# Audio_ADC.net
KiCad netlist of a schematic drawn in Altium Designer
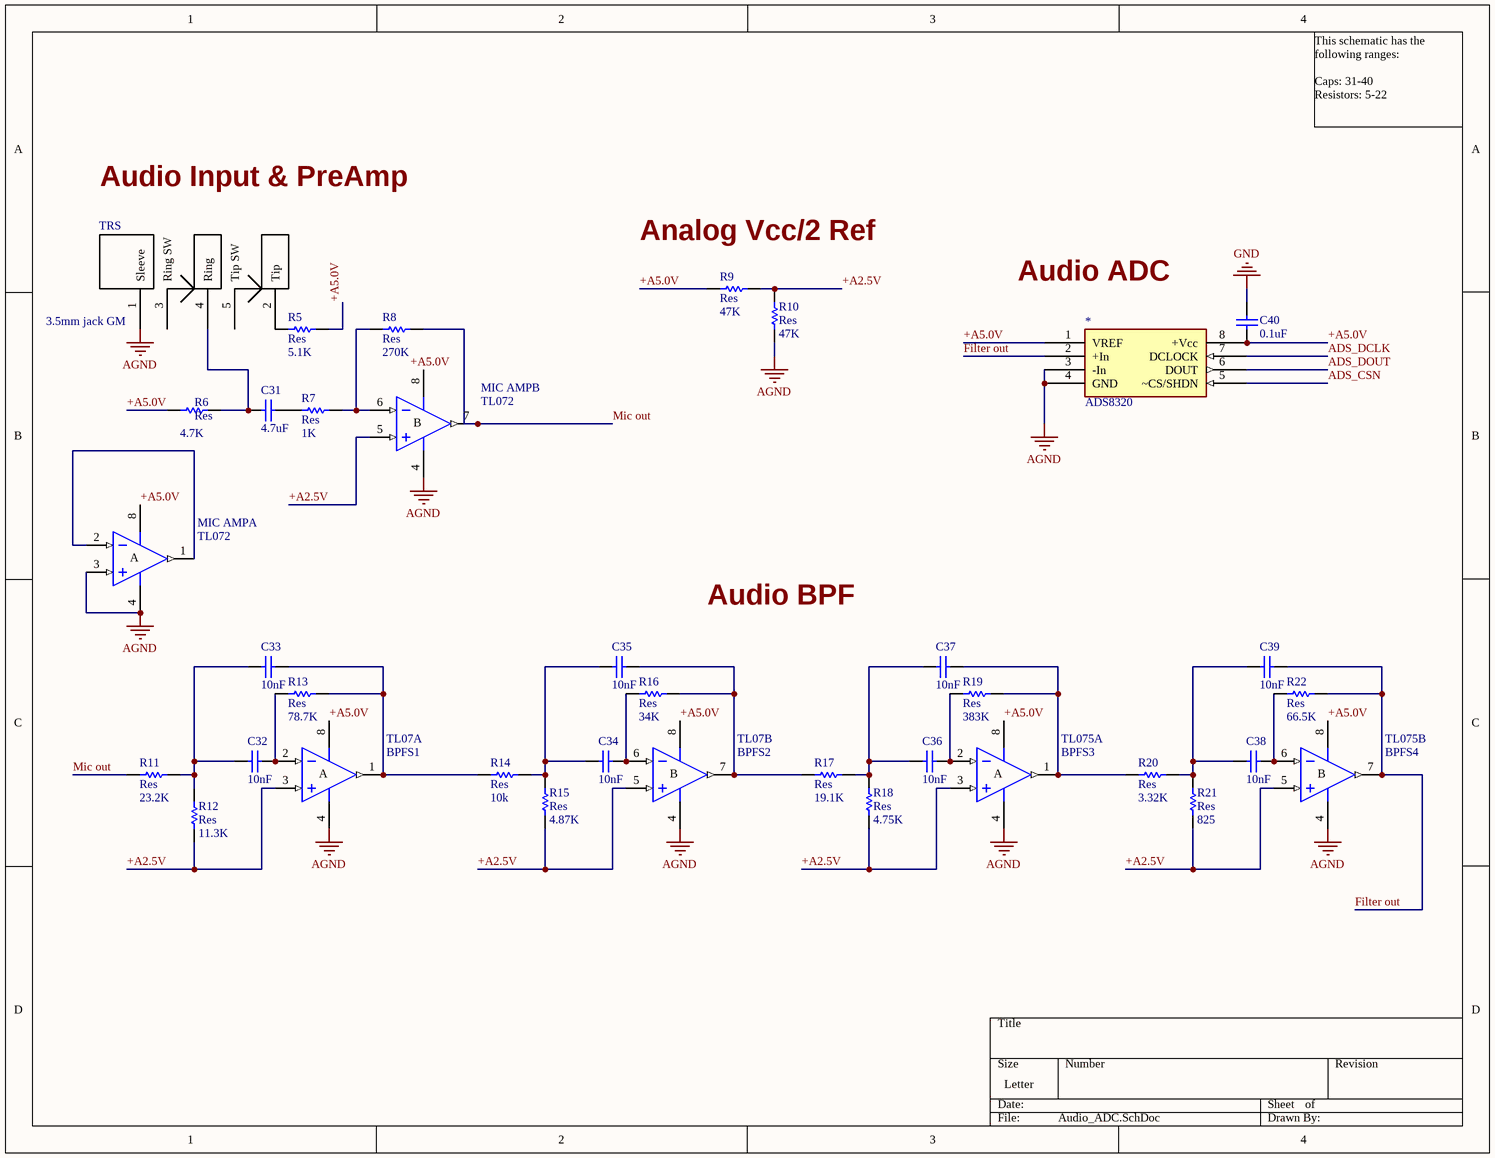
[diagram p0: Audio_ADC.SchDoc]

(export (version "E")
  (design (tool "Eeschema 10.0.6"))
  (components
    (comp (ref "*")
      (value "ADS8320")
      (footprint "TSOP65P490X110-8N")
      (libsource (lib "ADS8320") (part "ADS8320"))
    )
    (comp (ref "C31")
      (value "4.7uF")
      (footprint "0805")
      (description "Capacitor (Semiconductor SIM Model)")
      (fields (field (name "Comment") "Cap Semi") (field (name "PUBLISHER") "Altium Limited"))
      (libsource (lib "TMS320F28335GF") (part "Cap Semi"))
    )
    (comp (ref "C32")
      (value "10nF")
      (footprint "0805")
      (description "Capacitor (Semiconductor SIM Model)")
      (fields (field (name "Comment") "Cap Semi") (field (name "PUBLISHER") "Altium Limited"))
      (libsource (lib "TMS320F28335GF") (part "Cap Semi"))
    )
    (comp (ref "C33")
      (value "10nF")
      (footprint "0805")
      (description "Capacitor (Semiconductor SIM Model)")
      (fields (field (name "Comment") "Cap Semi") (field (name "PUBLISHER") "Altium Limited"))
      (libsource (lib "TMS320F28335GF") (part "Cap Semi"))
    )
    (comp (ref "C34")
      (value "10nF")
      (footprint "0805")
      (description "Capacitor (Semiconductor SIM Model)")
      (fields (field (name "Comment") "Cap Semi") (field (name "PUBLISHER") "Altium Limited"))
      (libsource (lib "TMS320F28335GF") (part "Cap Semi"))
    )
    (comp (ref "C35")
      (value "10nF")
      (footprint "0805")
      (description "Capacitor (Semiconductor SIM Model)")
      (fields (field (name "Comment") "Cap Semi") (field (name "PUBLISHER") "Altium Limited"))
      (libsource (lib "TMS320F28335GF") (part "Cap Semi"))
    )
    (comp (ref "C36")
      (value "10nF")
      (footprint "0805")
      (description "Capacitor (Semiconductor SIM Model)")
      (fields (field (name "Comment") "Cap Semi") (field (name "PUBLISHER") "Altium Limited"))
      (libsource (lib "TMS320F28335GF") (part "Cap Semi"))
    )
    (comp (ref "C37")
      (value "10nF")
      (footprint "0805")
      (description "Capacitor (Semiconductor SIM Model)")
      (fields (field (name "Comment") "Cap Semi") (field (name "PUBLISHER") "Altium Limited"))
      (libsource (lib "TMS320F28335GF") (part "Cap Semi"))
    )
    (comp (ref "C38")
      (value "10nF")
      (footprint "0805")
      (description "Capacitor (Semiconductor SIM Model)")
      (fields (field (name "Comment") "Cap Semi") (field (name "PUBLISHER") "Altium Limited"))
      (libsource (lib "TMS320F28335GF") (part "Cap Semi"))
    )
    (comp (ref "C39")
      (value "10nF")
      (footprint "0805")
      (description "Capacitor (Semiconductor SIM Model)")
      (fields (field (name "Comment") "Cap Semi") (field (name "PUBLISHER") "Altium Limited"))
      (libsource (lib "TMS320F28335GF") (part "Cap Semi"))
    )
    (comp (ref "C40")
      (value "0.1uF")
      (footprint "0805")
      (description "Capacitor (Semiconductor SIM Model)")
      (fields (field (name "Comment") "Cap Semi") (field (name "PUBLISHER") "Altium Limited"))
      (libsource (lib "TMS320F28335GF") (part "Cap Semi"))
    )
    (comp (ref "MIC AMP")
      (value "TL072")
      (footprint "DIP-8")
      (description "45MHz, 45V/µs, Dual Rail-to-Rail Input and Output Precision Operational Amplifier")
      (fields (field (name "PUBLISHER") "Altium Limited"))
      (libsource (lib "ECE LIB new") (part "LT1632CN8"))
    )
    (comp (ref "R5")
      (value "Res")
      (footprint "0805")
      (description "Semiconductor Resistor")
      (fields (field (name "ALTIUM_VALUE") "5.1K") (field (name "PUBLISHER") "Altium Limited"))
      (libsource (lib "TMS320F28335GF") (part "Res Semi"))
    )
    (comp (ref "R6")
      (value "Res")
      (footprint "0805")
      (description "Semiconductor Resistor")
      (fields (field (name "ALTIUM_VALUE") "4.7K") (field (name "PUBLISHER") "Altium Limited"))
      (libsource (lib "TMS320F28335GF") (part "Res Semi"))
    )
    (comp (ref "R7")
      (value "Res")
      (footprint "0805")
      (description "Semiconductor Resistor")
      (fields (field (name "ALTIUM_VALUE") "1K") (field (name "PUBLISHER") "Altium Limited"))
      (libsource (lib "TMS320F28335GF") (part "Res Semi"))
    )
    (comp (ref "R8")
      (value "Res")
      (footprint "0805")
      (description "Semiconductor Resistor")
      (fields (field (name "ALTIUM_VALUE") "270K") (field (name "PUBLISHER") "Altium Limited"))
      (libsource (lib "TMS320F28335GF") (part "Res Semi"))
    )
    (comp (ref "R9")
      (value "Res")
      (footprint "0805")
      (description "Semiconductor Resistor")
      (fields (field (name "ALTIUM_VALUE") "47K") (field (name "PUBLISHER") "Altium Limited"))
      (libsource (lib "TMS320F28335GF") (part "Res Semi"))
    )
    (comp (ref "R10")
      (value "Res")
      (footprint "0805")
      (description "Semiconductor Resistor")
      (fields (field (name "ALTIUM_VALUE") "47K") (field (name "PUBLISHER") "Altium Limited"))
      (libsource (lib "TMS320F28335GF") (part "Res Semi"))
    )
    (comp (ref "R11")
      (value "Res")
      (footprint "0805")
      (description "Semiconductor Resistor")
      (fields (field (name "ALTIUM_VALUE") "23.2K") (field (name "PUBLISHER") "Altium Limited"))
      (libsource (lib "TMS320F28335GF") (part "Res Semi"))
    )
    (comp (ref "R12")
      (value "Res")
      (footprint "0805")
      (description "Semiconductor Resistor")
      (fields (field (name "ALTIUM_VALUE") "11.3K") (field (name "PUBLISHER") "Altium Limited"))
      (libsource (lib "TMS320F28335GF") (part "Res Semi"))
    )
    (comp (ref "R13")
      (value "Res")
      (footprint "0805")
      (description "Semiconductor Resistor")
      (fields (field (name "ALTIUM_VALUE") "78.7K") (field (name "PUBLISHER") "Altium Limited"))
      (libsource (lib "TMS320F28335GF") (part "Res Semi"))
    )
    (comp (ref "R14")
      (value "Res")
      (footprint "0805")
      (description "Semiconductor Resistor")
      (fields (field (name "ALTIUM_VALUE") "10k") (field (name "PUBLISHER") "Altium Limited"))
      (libsource (lib "TMS320F28335GF") (part "Res Semi"))
    )
    (comp (ref "R15")
      (value "Res")
      (footprint "0805")
      (description "Semiconductor Resistor")
      (fields (field (name "ALTIUM_VALUE") "4.87K") (field (name "PUBLISHER") "Altium Limited"))
      (libsource (lib "TMS320F28335GF") (part "Res Semi"))
    )
    (comp (ref "R16")
      (value "Res")
      (footprint "0805")
      (description "Semiconductor Resistor")
      (fields (field (name "ALTIUM_VALUE") "34K") (field (name "PUBLISHER") "Altium Limited"))
      (libsource (lib "TMS320F28335GF") (part "Res Semi"))
    )
    (comp (ref "R17")
      (value "Res")
      (footprint "0805")
      (description "Semiconductor Resistor")
      (fields (field (name "ALTIUM_VALUE") "19.1K") (field (name "PUBLISHER") "Altium Limited"))
      (libsource (lib "TMS320F28335GF") (part "Res Semi"))
    )
    (comp (ref "R18")
      (value "Res")
      (footprint "0805")
      (description "Semiconductor Resistor")
      (fields (field (name "ALTIUM_VALUE") "4.75K") (field (name "PUBLISHER") "Altium Limited"))
      (libsource (lib "TMS320F28335GF") (part "Res Semi"))
    )
    (comp (ref "R19")
      (value "Res")
      (footprint "0805")
      (description "Semiconductor Resistor")
      (fields (field (name "ALTIUM_VALUE") "383K") (field (name "PUBLISHER") "Altium Limited"))
      (libsource (lib "TMS320F28335GF") (part "Res Semi"))
    )
    (comp (ref "R20")
      (value "Res")
      (footprint "0805")
      (description "Semiconductor Resistor")
      (fields (field (name "ALTIUM_VALUE") "3.32K") (field (name "PUBLISHER") "Altium Limited"))
      (libsource (lib "TMS320F28335GF") (part "Res Semi"))
    )
    (comp (ref "R21")
      (value "Res")
      (footprint "0805")
      (description "Semiconductor Resistor")
      (fields (field (name "ALTIUM_VALUE") "825") (field (name "PUBLISHER") "Altium Limited"))
      (libsource (lib "TMS320F28335GF") (part "Res Semi"))
    )
    (comp (ref "R22")
      (value "Res")
      (footprint "0805")
      (description "Semiconductor Resistor")
      (fields (field (name "ALTIUM_VALUE") "66.5K") (field (name "PUBLISHER") "Altium Limited"))
      (libsource (lib "TMS320F28335GF") (part "Res Semi"))
    )
    (comp (ref "TL07")
      (value "BPFS2")
      (footprint "DIP-8")
      (description "45MHz, 45V/µs, Dual Rail-to-Rail Input and Output Precision Operational Amplifier")
      (fields (field (name "PUBLISHER") "Altium Limited"))
      (libsource (lib "ECE LIB new") (part "LT1632CN8"))
    )
    (comp (ref "TL075")
      (value "BPFS3")
      (footprint "DIP-8")
      (description "45MHz, 45V/µs, Dual Rail-to-Rail Input and Output Precision Operational Amplifier")
      (fields (field (name "PUBLISHER") "Altium Limited"))
      (libsource (lib "ECE LIB new") (part "LT1632CN8"))
    )
    (comp (ref "TRS")
      (value "3.5mm jack GM")
      (footprint "3.5mm jack GM")
      (libsource (lib "ECE LIB new") (part "3.5mm jack GM"))
    )
  )
  (nets
    (net (code "1") (name "/+A2.5V") (class "Default")
      (node (ref "MIC AMP") (pin "5") (pinfunction "IN+_5") (pintype "input"))
      (node (ref "R10") (pin "2") (pinfunction "2_2") (pintype "passive"))
      (node (ref "R12") (pin "2") (pinfunction "2_2") (pintype "passive"))
      (node (ref "R15") (pin "1") (pinfunction "1_1") (pintype "passive"))
      (node (ref "R18") (pin "1") (pinfunction "1_1") (pintype "passive"))
      (node (ref "R21") (pin "1") (pinfunction "1_1") (pintype "passive"))
      (node (ref "R9") (pin "1") (pinfunction "1_1") (pintype "passive"))
      (node (ref "TL07") (pin "3") (pinfunction "IN+_3") (pintype "input"))
      (node (ref "TL07") (pin "5") (pinfunction "IN+_5") (pintype "input"))
      (node (ref "TL075") (pin "3") (pinfunction "IN+_3") (pintype "input"))
      (node (ref "TL075") (pin "5") (pinfunction "IN+_5") (pintype "input"))
    )
    (net (code "2") (name "/+A5.0V") (class "Default")
      (node (ref "*") (pin "1") (pinfunction "VREF_1") (pintype "power_in"))
      (node (ref "*") (pin "8") (pinfunction "+Vcc_8") (pintype "power_in"))
      (node (ref "C40") (pin "1") (pinfunction "1_1") (pintype "passive"))
      (node (ref "MIC AMP") (pin "8") (pinfunction "V+_8") (pintype "power_in"))
      (node (ref "R5") (pin "1") (pinfunction "1_1") (pintype "passive"))
      (node (ref "R6") (pin "2") (pinfunction "2_2") (pintype "passive"))
      (node (ref "R9") (pin "2") (pinfunction "2_2") (pintype "passive"))
      (node (ref "TL07") (pin "8") (pinfunction "V+_8") (pintype "power_in"))
      (node (ref "TL075") (pin "8") (pinfunction "V+_8") (pintype "power_in"))
    )
    (net (code "3") (name "/ADS_CSN") (class "Default")
      (node (ref "*") (pin "5") (pinfunction "~CS/SHDN_5") (pintype "input"))
    )
    (net (code "4") (name "/ADS_DCLK") (class "Default")
      (node (ref "*") (pin "7") (pinfunction "DCLOCK_7") (pintype "input"))
    )
    (net (code "5") (name "/ADS_DOUT") (class "Default")
      (node (ref "*") (pin "6") (pinfunction "DOUT_6") (pintype "output"))
    )
    (net (code "6") (name "/Filter out") (class "Default")
      (node (ref "*") (pin "2") (pinfunction "+In_2") (pintype "power_in"))
      (node (ref "C39") (pin "2") (pinfunction "2_2") (pintype "passive"))
      (node (ref "R22") (pin "1") (pinfunction "1_1") (pintype "passive"))
      (node (ref "TL075") (pin "7") (pinfunction "OUT_7") (pintype "output"))
    )
    (net (code "7") (name "/Mic out") (class "Default")
      (node (ref "MIC AMP") (pin "7") (pinfunction "OUT_7") (pintype "output"))
      (node (ref "R11") (pin "2") (pinfunction "2_2") (pintype "passive"))
      (node (ref "R8") (pin "1") (pinfunction "1_1") (pintype "passive"))
    )
    (net (code "8") (name "AGND") (class "Default")
      (node (ref "*") (pin "3") (pinfunction "-In_3") (pintype "power_in"))
      (node (ref "*") (pin "4") (pinfunction "GND_4") (pintype "power_in"))
      (node (ref "MIC AMP") (pin "3") (pinfunction "IN+_3") (pintype "input"))
      (node (ref "MIC AMP") (pin "4") (pinfunction "V-_4") (pintype "power_in"))
      (node (ref "R10") (pin "1") (pinfunction "1_1") (pintype "passive"))
      (node (ref "TL07") (pin "4") (pinfunction "V-_4") (pintype "power_in"))
      (node (ref "TL075") (pin "4") (pinfunction "V-_4") (pintype "power_in"))
      (node (ref "TRS") (pin "1") (pinfunction "Sleeve_1") (pintype "passive"))
    )
    (net (code "9") (name "GND") (class "Default")
      (node (ref "C40") (pin "2") (pinfunction "2_2") (pintype "passive"))
    )
    (net (code "10") (name "Net-(C31-Pad2)") (class "Default")
      (node (ref "C31") (pin "2") (pinfunction "2_2") (pintype "passive"))
      (node (ref "R7") (pin "2") (pinfunction "2_2") (pintype "passive"))
    )
    (net (code "11") (name "Net-(C32-Pad1)") (class "Default")
      (node (ref "C32") (pin "1") (pinfunction "1_1") (pintype "passive"))
      (node (ref "C33") (pin "1") (pinfunction "1_1") (pintype "passive"))
      (node (ref "R11") (pin "1") (pinfunction "1_1") (pintype "passive"))
      (node (ref "R12") (pin "1") (pinfunction "1_1") (pintype "passive"))
    )
    (net (code "12") (name "Net-(C34-Pad1)") (class "Default")
      (node (ref "C34") (pin "1") (pinfunction "1_1") (pintype "passive"))
      (node (ref "C35") (pin "1") (pinfunction "1_1") (pintype "passive"))
      (node (ref "R14") (pin "1") (pinfunction "1_1") (pintype "passive"))
      (node (ref "R15") (pin "2") (pinfunction "2_2") (pintype "passive"))
    )
    (net (code "13") (name "Net-(C36-Pad1)") (class "Default")
      (node (ref "C36") (pin "1") (pinfunction "1_1") (pintype "passive"))
      (node (ref "C37") (pin "1") (pinfunction "1_1") (pintype "passive"))
      (node (ref "R17") (pin "1") (pinfunction "1_1") (pintype "passive"))
      (node (ref "R18") (pin "2") (pinfunction "2_2") (pintype "passive"))
    )
    (net (code "14") (name "Net-(C38-Pad1)") (class "Default")
      (node (ref "C38") (pin "1") (pinfunction "1_1") (pintype "passive"))
      (node (ref "C39") (pin "1") (pinfunction "1_1") (pintype "passive"))
      (node (ref "R20") (pin "1") (pinfunction "1_1") (pintype "passive"))
      (node (ref "R21") (pin "2") (pinfunction "2_2") (pintype "passive"))
    )
    (net (code "15") (name "Net-(MIC AMPA-IN-)") (class "Default")
      (node (ref "MIC AMP") (pin "1") (pinfunction "OUT_1") (pintype "output"))
      (node (ref "MIC AMP") (pin "2") (pinfunction "IN-_2") (pintype "input"))
    )
    (net (code "16") (name "Net-(MIC AMPB-IN-)") (class "Default")
      (node (ref "MIC AMP") (pin "6") (pinfunction "IN-_6") (pintype "input"))
      (node (ref "R7") (pin "1") (pinfunction "1_1") (pintype "passive"))
      (node (ref "R8") (pin "2") (pinfunction "2_2") (pintype "passive"))
    )
    (net (code "17") (name "Net-(TL07A-IN-)") (class "Default")
      (node (ref "C32") (pin "2") (pinfunction "2_2") (pintype "passive"))
      (node (ref "R13") (pin "2") (pinfunction "2_2") (pintype "passive"))
      (node (ref "TL07") (pin "2") (pinfunction "IN-_2") (pintype "input"))
    )
    (net (code "18") (name "Net-(TL07A-OUT)") (class "Default")
      (node (ref "C33") (pin "2") (pinfunction "2_2") (pintype "passive"))
      (node (ref "R13") (pin "1") (pinfunction "1_1") (pintype "passive"))
      (node (ref "R14") (pin "2") (pinfunction "2_2") (pintype "passive"))
      (node (ref "TL07") (pin "1") (pinfunction "OUT_1") (pintype "output"))
    )
    (net (code "19") (name "Net-(TL07B-IN-)") (class "Default")
      (node (ref "C34") (pin "2") (pinfunction "2_2") (pintype "passive"))
      (node (ref "R16") (pin "2") (pinfunction "2_2") (pintype "passive"))
      (node (ref "TL07") (pin "6") (pinfunction "IN-_6") (pintype "input"))
    )
    (net (code "20") (name "Net-(TL07B-OUT)") (class "Default")
      (node (ref "C35") (pin "2") (pinfunction "2_2") (pintype "passive"))
      (node (ref "R16") (pin "1") (pinfunction "1_1") (pintype "passive"))
      (node (ref "R17") (pin "2") (pinfunction "2_2") (pintype "passive"))
      (node (ref "TL07") (pin "7") (pinfunction "OUT_7") (pintype "output"))
    )
    (net (code "21") (name "Net-(TL075A-IN-)") (class "Default")
      (node (ref "C36") (pin "2") (pinfunction "2_2") (pintype "passive"))
      (node (ref "R19") (pin "2") (pinfunction "2_2") (pintype "passive"))
      (node (ref "TL075") (pin "2") (pinfunction "IN-_2") (pintype "input"))
    )
    (net (code "22") (name "Net-(TL075A-OUT)") (class "Default")
      (node (ref "C37") (pin "2") (pinfunction "2_2") (pintype "passive"))
      (node (ref "R19") (pin "1") (pinfunction "1_1") (pintype "passive"))
      (node (ref "R20") (pin "2") (pinfunction "2_2") (pintype "passive"))
      (node (ref "TL075") (pin "1") (pinfunction "OUT_1") (pintype "output"))
    )
    (net (code "23") (name "Net-(TL075B-IN-)") (class "Default")
      (node (ref "C38") (pin "2") (pinfunction "2_2") (pintype "passive"))
      (node (ref "R22") (pin "2") (pinfunction "2_2") (pintype "passive"))
      (node (ref "TL075") (pin "6") (pinfunction "IN-_6") (pintype "input"))
    )
    (net (code "24") (name "Net-(TRS-Ring)") (class "Default")
      (node (ref "C31") (pin "1") (pinfunction "1_1") (pintype "passive"))
      (node (ref "R6") (pin "1") (pinfunction "1_1") (pintype "passive"))
      (node (ref "TRS") (pin "4") (pinfunction "Ring_4") (pintype "passive"))
    )
    (net (code "25") (name "Net-(TRS-Tip)") (class "Default")
      (node (ref "R5") (pin "2") (pinfunction "2_2") (pintype "passive"))
      (node (ref "TRS") (pin "2") (pinfunction "Tip_2") (pintype "passive"))
    )
    (net (code "26") (name "unconnected-(MIC AMPB-V+-Pad8)") (class "Default")
      (node (ref "MIC AMP") (pin "8") (pinfunction "V+_8") (pintype "power_in"))
    )
    (net (code "27") (name "unconnected-(TRS-Ring_SW-Pad3)") (class "Default")
      (node (ref "TRS") (pin "3") (pinfunction "Ring_SW_3") (pintype "passive"))
    )
    (net (code "28") (name "unconnected-(TRS-Tip_SW-Pad5)") (class "Default")
      (node (ref "TRS") (pin "5") (pinfunction "Tip_SW_5") (pintype "passive"))
    )
  )
)
